# SparkFun_Temperatre_Sensor-STTS22H.net
KiCad netlist of a schematic drawn in EAGLE
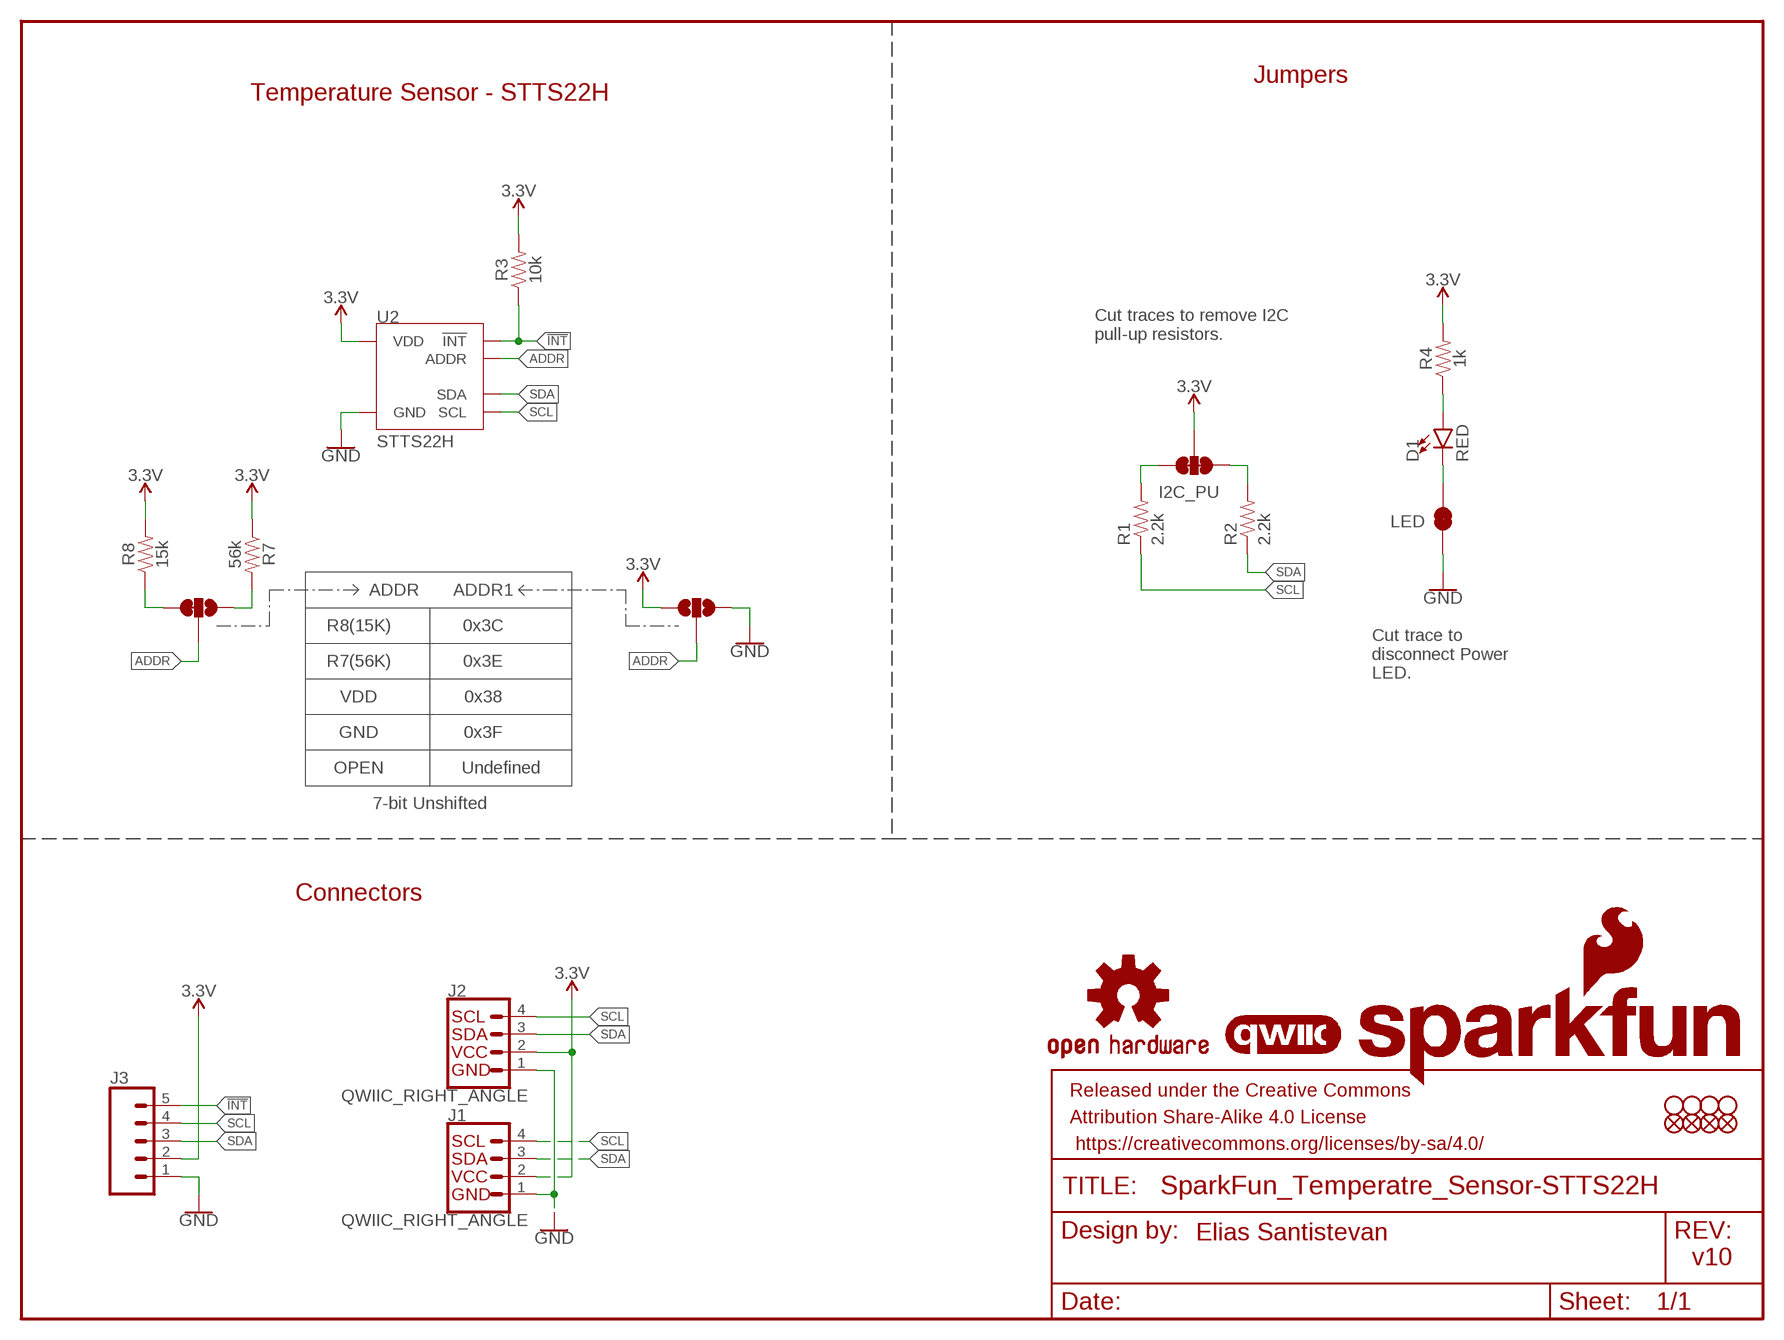
[diagram p0: schematic, sheet 1]

(export (version "E")
  (design (tool "Eeschema 10.0.6"))
  (components
    (comp (ref "ADDR")
      (value "JUMPER-SMT_3_1-NC_TRACE_SILK")
      (footprint "eagle-import:SMT-JUMPER_3_1-NC_TRACE_SILK")
      (libsource (lib "eagle-import") (part "JUMPER-SMT_3_1-NC_TRACE_SILK"))
    )
    (comp (ref "ADDR1")
      (value "JUMPER-SMT_3_NO_SILK")
      (footprint "eagle-import:SMT-JUMPER_3_NO_SILK")
      (libsource (lib "eagle-import") (part "JUMPER-SMT_3_NO_SILK"))
    )
    (comp (ref "D1")
      (value "RED")
      (footprint "eagle-import:LED-0603")
      (libsource (lib "eagle-import") (part "LED-RED0603"))
    )
    (comp (ref "FD1")
      (value "FIDUCIAL1X2")
      (footprint "eagle-import:FIDUCIAL-1X2")
      (libsource (lib "eagle-import") (part "FIDUCIAL1X2"))
    )
    (comp (ref "FD2")
      (value "FIDUCIAL1X2")
      (footprint "eagle-import:FIDUCIAL-1X2")
      (libsource (lib "eagle-import") (part "FIDUCIAL1X2"))
    )
    (comp (ref "FD3")
      (value "FIDUCIAL1X2")
      (footprint "eagle-import:FIDUCIAL-1X2")
      (libsource (lib "eagle-import") (part "FIDUCIAL1X2"))
    )
    (comp (ref "FD4")
      (value "FIDUCIAL1X2")
      (footprint "eagle-import:FIDUCIAL-1X2")
      (libsource (lib "eagle-import") (part "FIDUCIAL1X2"))
    )
    (comp (ref "FRAME1")
      (value "FRAME-LETTER")
      (footprint "eagle-import:CREATIVE_COMMONS")
      (fields (field (name "DESIGNER") "Elias Santistevan"))
      (libsource (lib "eagle-import") (part "FRAME-LETTER"))
    )
    (comp (ref "I2C_PU")
      (value "S_MODE")
      (footprint "eagle-import:SMT-JUMPER_3_2-NC_TRACE_SILK")
      (libsource (lib "eagle-import") (part "JUMPER-SMT_3_2-NC_TRACE_SILK"))
    )
    (comp (ref "J1")
      (value "QWIIC_RIGHT_ANGLE")
      (footprint "eagle-import:JST04_1MM_RA")
      (libsource (lib "eagle-import") (part "QWIIC_CONNECTORJS-1MM"))
    )
    (comp (ref "J2")
      (value "QWIIC_RIGHT_ANGLE")
      (footprint "eagle-import:JST04_1MM_RA")
      (libsource (lib "eagle-import") (part "QWIIC_CONNECTORJS-1MM"))
    )
    (comp (ref "J3")
      (value "CONN_05NO_SILK")
      (footprint "eagle-import:1X05_NO_SILK")
      (libsource (lib "eagle-import") (part "CONN_05NO_SILK"))
    )
    (comp (ref "LED")
      (value "JUMPER-SMT_2_NC_TRACE_SILK")
      (footprint "eagle-import:SMT-JUMPER_2_NC_TRACE_SILK")
      (libsource (lib "eagle-import") (part "JUMPER-SMT_2_NC_TRACE_SILK"))
    )
    (comp (ref "LOGO2")
      (value "OSHW-LOGOMINI")
      (footprint "eagle-import:OSHW-LOGO-MINI")
      (libsource (lib "eagle-import") (part "OSHW-LOGOMINI"))
    )
    (comp (ref "LOGO3")
      (value "SFE_LOGO_NAME_FLAME.1_INCH")
      (footprint "eagle-import:SFE_LOGO_NAME_FLAME_.1")
      (libsource (lib "eagle-import") (part "SFE_LOGO_NAME_FLAME.1_INCH"))
    )
    (comp (ref "LOGO4")
      (value "QWIIC_LOGO_4MM")
      (footprint "eagle-import:QWIIC_4MM")
      (libsource (lib "eagle-import") (part "QWIIC_LOGO_4MM"))
    )
    (comp (ref "R1")
      (value "2.2k")
      (footprint "eagle-import:0603")
      (libsource (lib "eagle-import") (part "2.2KOHM-0603-1/10W-1%"))
    )
    (comp (ref "R2")
      (value "2.2k")
      (footprint "eagle-import:0603")
      (libsource (lib "eagle-import") (part "2.2KOHM-0603-1/10W-1%"))
    )
    (comp (ref "R3")
      (value "10k")
      (footprint "eagle-import:0603")
      (libsource (lib "eagle-import") (part "10KOHM-0603-1/10W-1%"))
    )
    (comp (ref "R4")
      (value "1k")
      (footprint "eagle-import:0603")
      (libsource (lib "eagle-import") (part "1KOHM-0603-1/10W-1%"))
    )
    (comp (ref "R7")
      (value "56k")
      (footprint "eagle-import:0603")
      (libsource (lib "eagle-import") (part "56KOHM"))
    )
    (comp (ref "R8")
      (value "15k")
      (footprint "eagle-import:0603")
      (libsource (lib "eagle-import") (part "15KOHM-0603-1/10W-1%"))
    )
    (comp (ref "STANDOFF1")
      (value "STAND-OFFTIGHT")
      (footprint "eagle-import:STAND-OFF-TIGHT")
      (libsource (lib "eagle-import") (part "STAND-OFFTIGHT"))
    )
    (comp (ref "STANDOFF2")
      (value "STAND-OFFTIGHT")
      (footprint "eagle-import:STAND-OFF-TIGHT")
      (libsource (lib "eagle-import") (part "STAND-OFFTIGHT"))
    )
    (comp (ref "STANDOFF3")
      (value "STAND-OFFTIGHT")
      (footprint "eagle-import:STAND-OFF-TIGHT")
      (libsource (lib "eagle-import") (part "STAND-OFFTIGHT"))
    )
    (comp (ref "STANDOFF5")
      (value "STAND-OFFTIGHT")
      (footprint "eagle-import:STAND-OFF-TIGHT")
      (libsource (lib "eagle-import") (part "STAND-OFFTIGHT"))
    )
    (comp (ref "U2")
      (value "STTS22H")
      (footprint "eagle-import:UDFN-6L")
      (libsource (lib "eagle-import") (part "STTS22H"))
    )
  )
  (nets
    (net (code "1") (name "/~{INT}") (class "Default")
      (node (ref "J3") (pin "5") (pinfunction "5_5") (pintype "passive"))
      (node (ref "R3") (pin "1") (pinfunction "1_1") (pintype "passive"))
      (node (ref "U2") (pin "P2") (pinfunction "~{INT}_P2") (pintype "bidirectional"))
    )
    (net (code "2") (name "3.3V") (class "Default")
      (node (ref "ADDR1") (pin "3") (pinfunction "3_3") (pintype "passive"))
      (node (ref "I2C_PU") (pin "2") (pinfunction "2_2") (pintype "passive"))
      (node (ref "J1") (pin "2") (pinfunction "2_2") (pintype "power_in"))
      (node (ref "J2") (pin "2") (pinfunction "2_2") (pintype "power_in"))
      (node (ref "J3") (pin "2") (pinfunction "2_2") (pintype "passive"))
      (node (ref "R3") (pin "2") (pinfunction "2_2") (pintype "passive"))
      (node (ref "R4") (pin "2") (pinfunction "2_2") (pintype "passive"))
      (node (ref "R7") (pin "1") (pinfunction "1_1") (pintype "passive"))
      (node (ref "R8") (pin "2") (pinfunction "2_2") (pintype "passive"))
      (node (ref "U2") (pin "P3") (pinfunction "VDD_P3") (pintype "power_in"))
    )
    (net (code "3") (name "ADDR") (class "Default")
      (node (ref "ADDR") (pin "2") (pinfunction "2_2") (pintype "passive"))
      (node (ref "ADDR1") (pin "2") (pinfunction "2_2") (pintype "passive"))
      (node (ref "U2") (pin "P4") (pinfunction "ADDR_P4") (pintype "bidirectional"))
    )
    (net (code "4") (name "GND") (class "Default")
      (node (ref "ADDR1") (pin "1") (pinfunction "1_1") (pintype "passive"))
      (node (ref "J1") (pin "1") (pinfunction "1_1") (pintype "power_in"))
      (node (ref "J2") (pin "1") (pinfunction "1_1") (pintype "power_in"))
      (node (ref "J3") (pin "1") (pinfunction "1_1") (pintype "passive"))
      (node (ref "LED") (pin "1") (pinfunction "1_1") (pintype "passive"))
      (node (ref "U2") (pin "P5") (pinfunction "GND_P5") (pintype "power_in"))
    )
    (net (code "5") (name "Net-(ADDR-Pad1)") (class "Default")
      (node (ref "ADDR") (pin "1") (pinfunction "1_1") (pintype "passive"))
      (node (ref "R7") (pin "2") (pinfunction "2_2") (pintype "passive"))
    )
    (net (code "6") (name "Net-(ADDR-Pad3)") (class "Default")
      (node (ref "ADDR") (pin "3") (pinfunction "3_3") (pintype "passive"))
      (node (ref "R8") (pin "1") (pinfunction "1_1") (pintype "passive"))
    )
    (net (code "7") (name "Net-(D1-PadA)") (class "Default")
      (node (ref "D1") (pin "A") (pinfunction "A_A") (pintype "passive"))
      (node (ref "R4") (pin "1") (pinfunction "1_1") (pintype "passive"))
    )
    (net (code "8") (name "Net-(D1-PadC)") (class "Default")
      (node (ref "D1") (pin "C") (pinfunction "C_C") (pintype "passive"))
      (node (ref "LED") (pin "2") (pinfunction "2_2") (pintype "passive"))
    )
    (net (code "9") (name "Net-(I2C_PU-Pad1)") (class "Default")
      (node (ref "I2C_PU") (pin "1") (pinfunction "1_1") (pintype "passive"))
      (node (ref "R1") (pin "2") (pinfunction "2_2") (pintype "passive"))
    )
    (net (code "10") (name "Net-(I2C_PU-Pad3)") (class "Default")
      (node (ref "I2C_PU") (pin "3") (pinfunction "3_3") (pintype "passive"))
      (node (ref "R2") (pin "2") (pinfunction "2_2") (pintype "passive"))
    )
    (net (code "11") (name "SCL") (class "Default")
      (node (ref "J1") (pin "4") (pinfunction "4_4") (pintype "passive"))
      (node (ref "J2") (pin "4") (pinfunction "4_4") (pintype "passive"))
      (node (ref "J3") (pin "4") (pinfunction "4_4") (pintype "passive"))
      (node (ref "R1") (pin "1") (pinfunction "1_1") (pintype "passive"))
      (node (ref "U2") (pin "P1") (pinfunction "SCL_P1") (pintype "bidirectional"))
    )
    (net (code "12") (name "SDA") (class "Default")
      (node (ref "J1") (pin "3") (pinfunction "3_3") (pintype "passive"))
      (node (ref "J2") (pin "3") (pinfunction "3_3") (pintype "passive"))
      (node (ref "J3") (pin "3") (pinfunction "3_3") (pintype "passive"))
      (node (ref "R2") (pin "1") (pinfunction "1_1") (pintype "passive"))
      (node (ref "U2") (pin "P6") (pinfunction "SDA_P6") (pintype "bidirectional"))
    )
  )
)
